# RGB_Bike_POV_v3.net
KiCad netlist of a schematic drawn in EAGLE
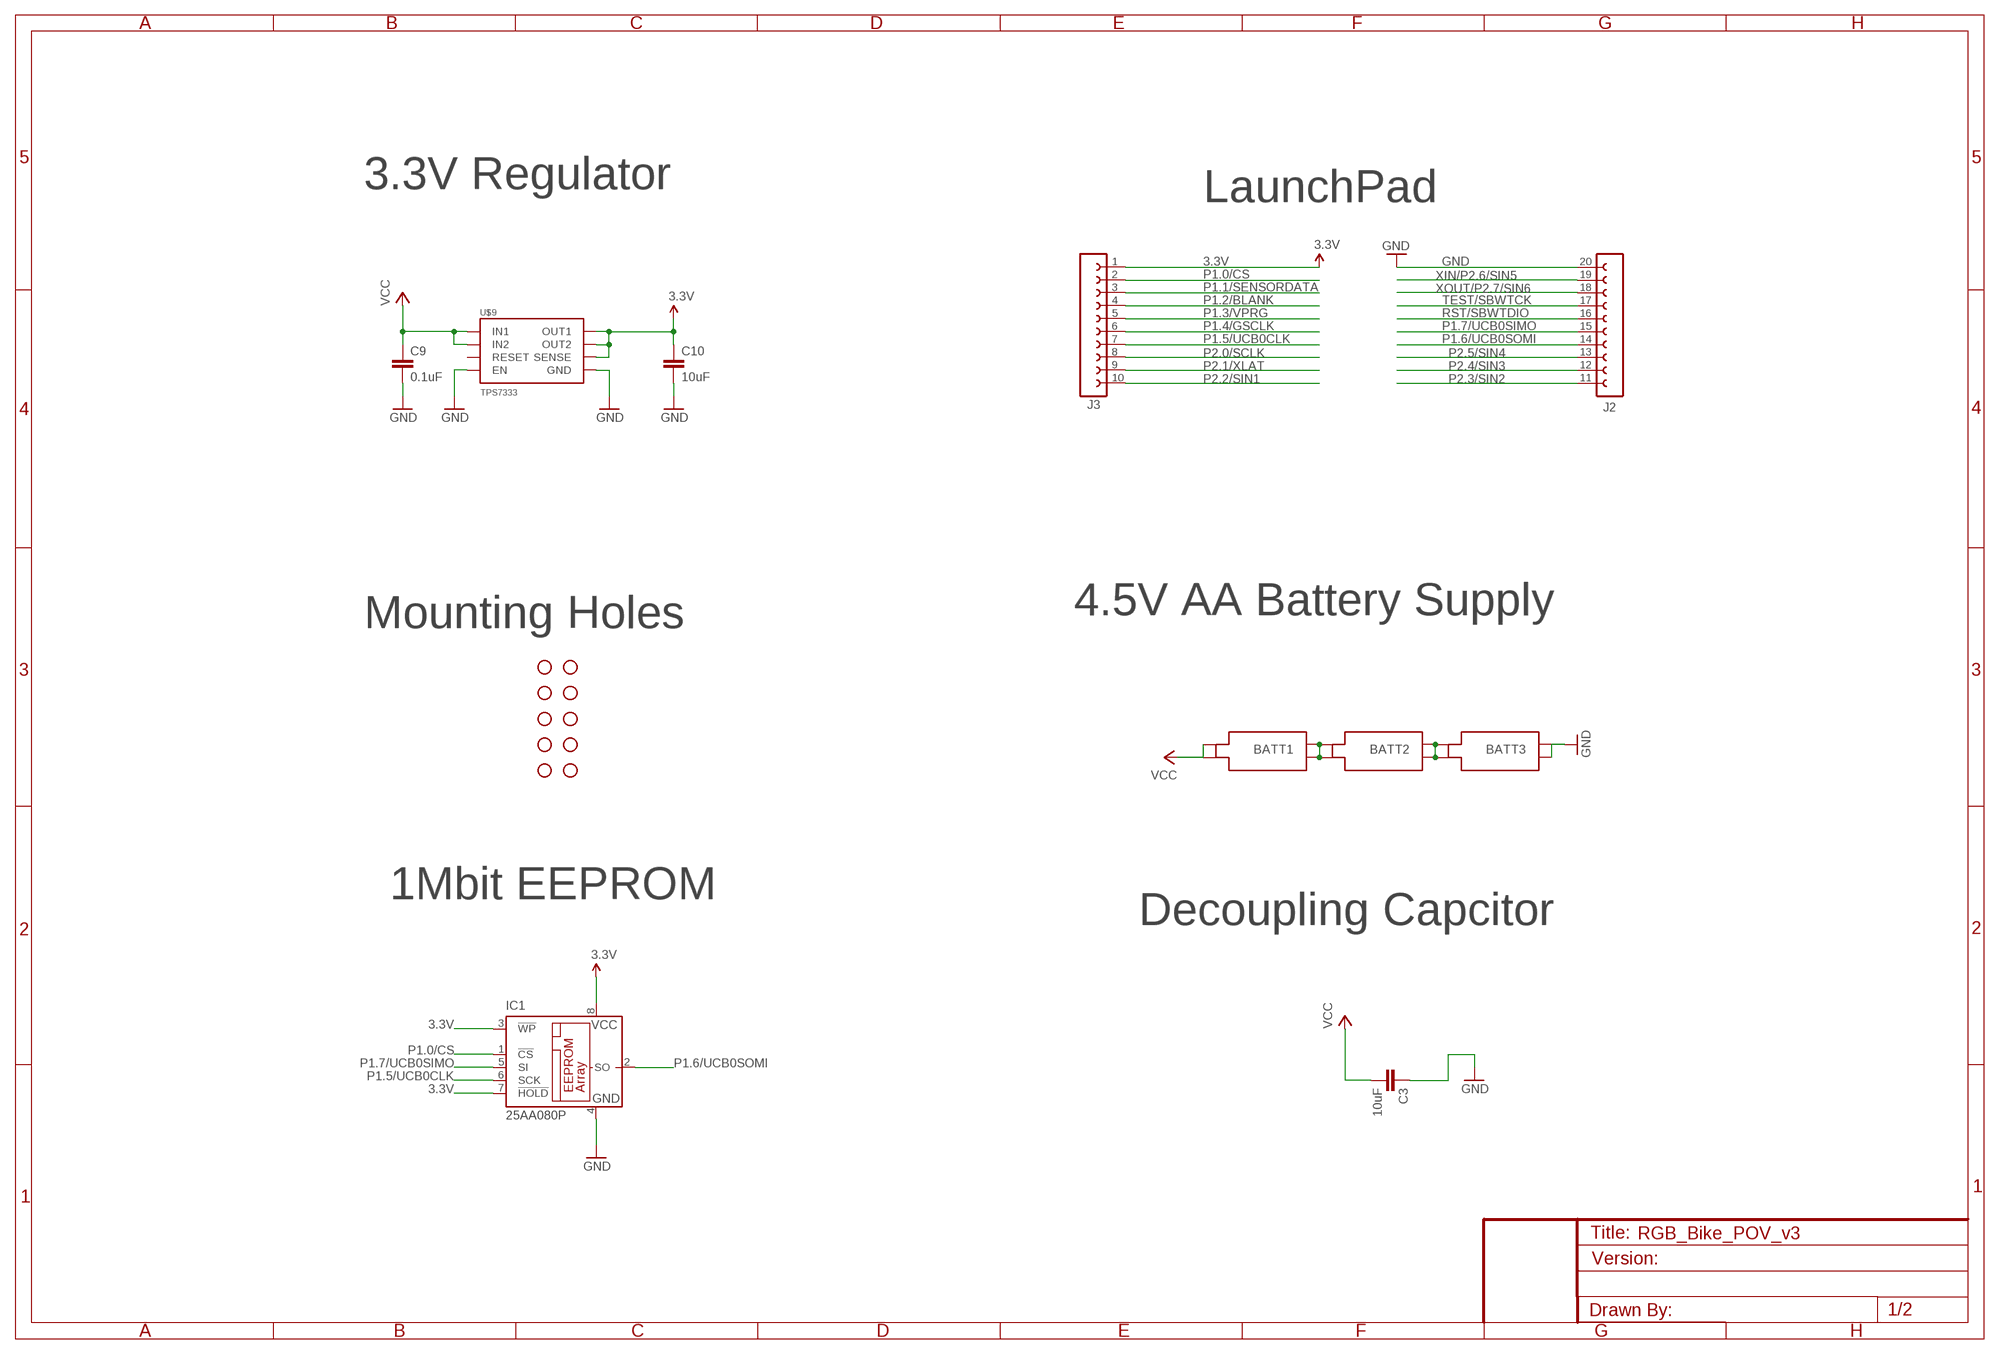
[diagram p0: schematic, sheet 1]
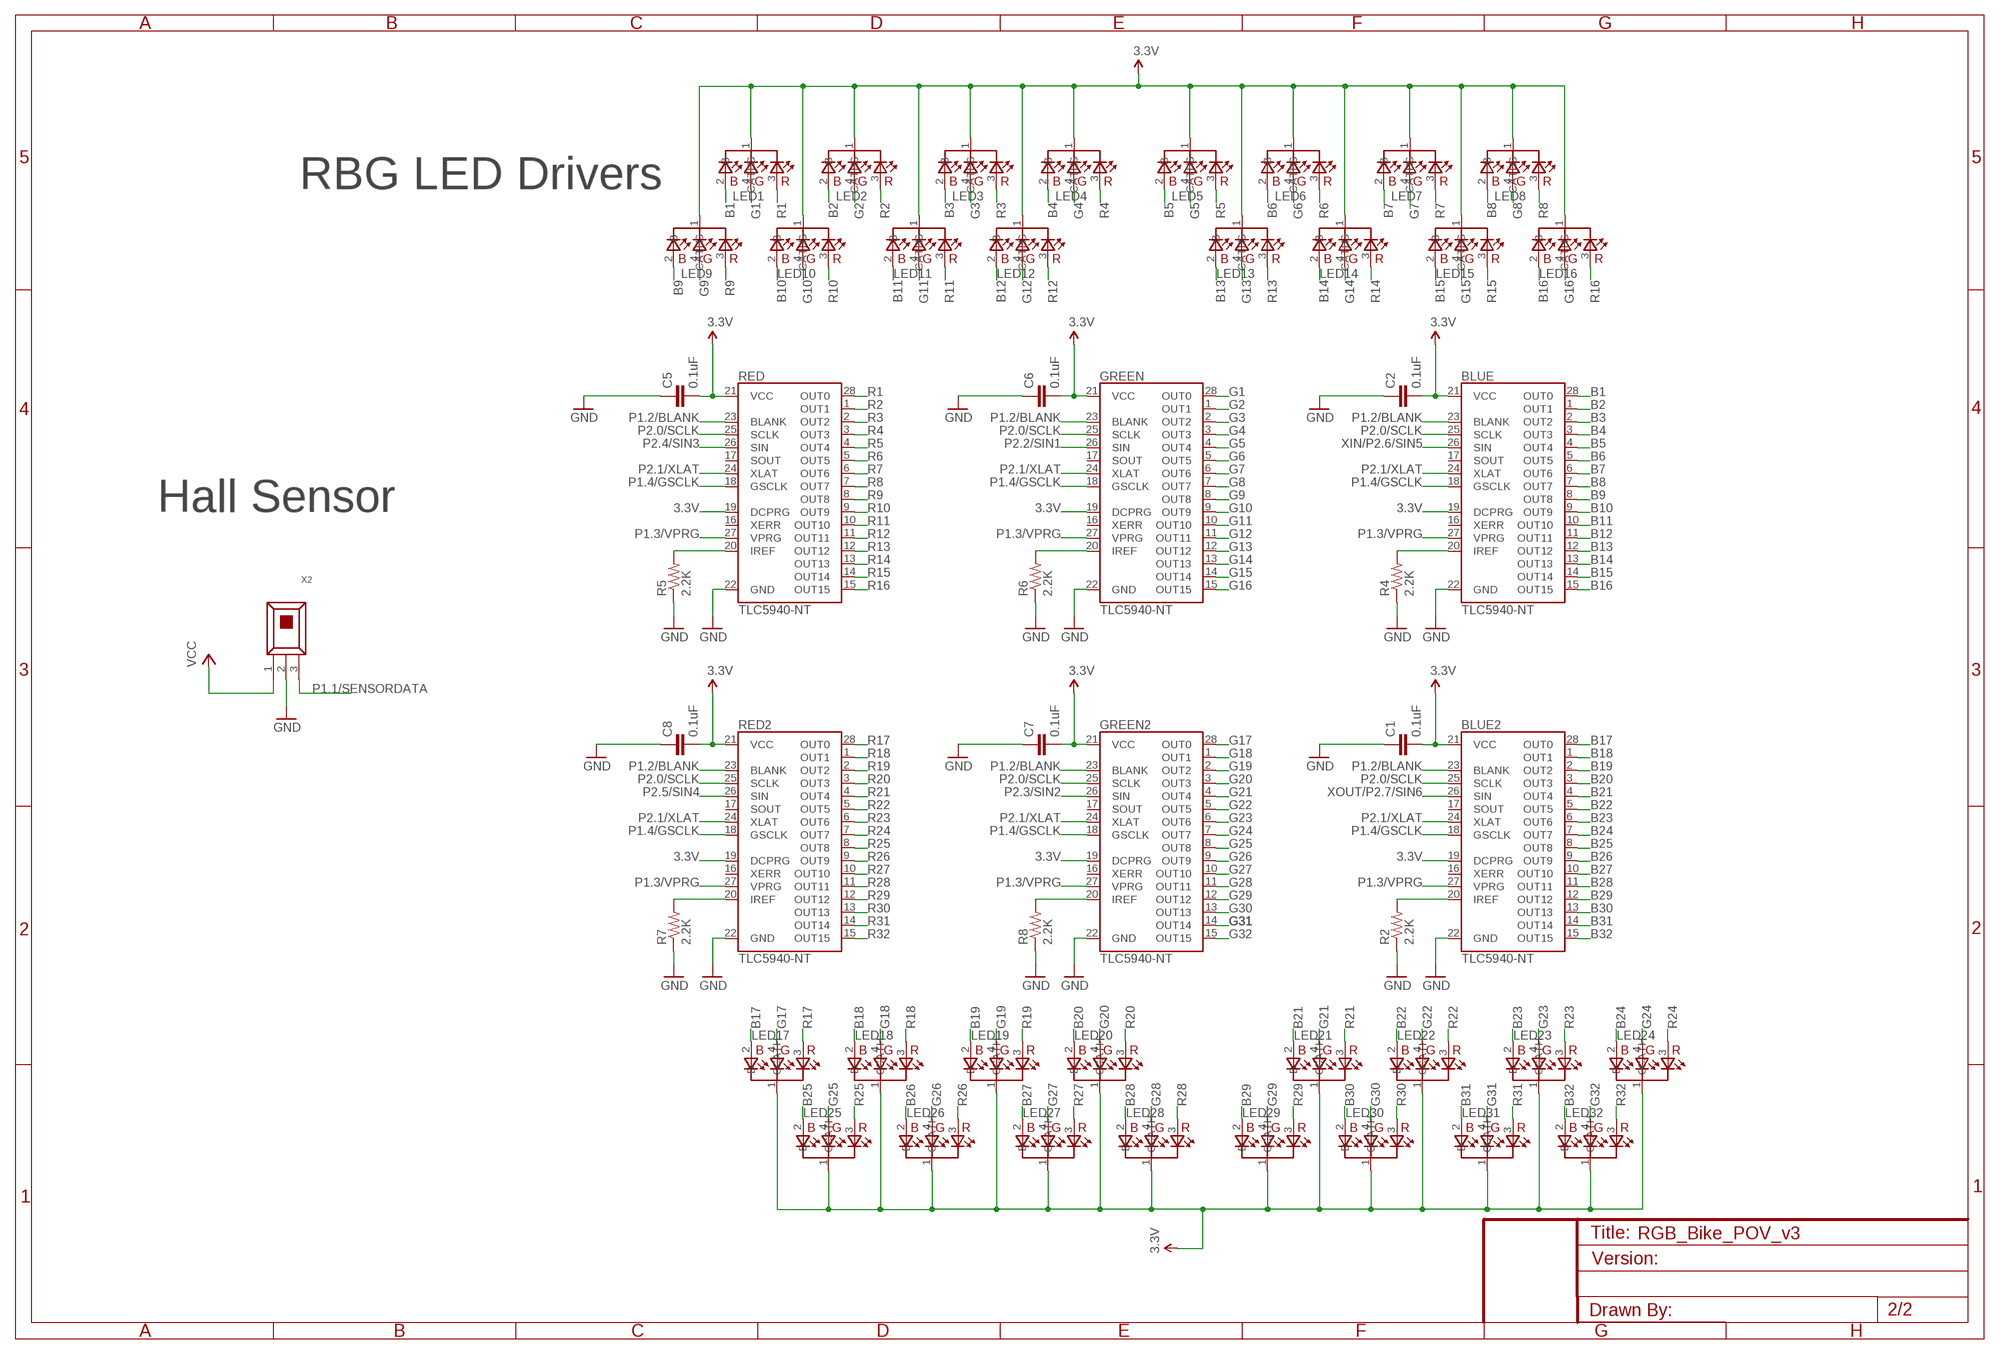
[diagram p1: schematic, sheet 2]

(export (version "E")
  (design (tool "Eeschema 10.0.6"))
  (components
    (comp (ref "BATT1")
      (value "1XAA")
      (footprint "eagle-import:1XAA")
      (libsource (lib "eagle-import") (part "1XAA"))
    )
    (comp (ref "BATT2")
      (value "1XAA")
      (footprint "eagle-import:1XAA")
      (libsource (lib "eagle-import") (part "1XAA"))
    )
    (comp (ref "BATT3")
      (value "1XAA")
      (footprint "eagle-import:1XAA")
      (libsource (lib "eagle-import") (part "1XAA"))
    )
    (comp (ref "C3")
      (value "10uF")
      (footprint "eagle-import:CAP-PTH-SMALL")
      (libsource (lib "eagle-import") (part "CAPPTH"))
    )
    (comp (ref "C9")
      (value "0.1uF")
      (footprint "eagle-import:CAP-PTH-SMALL")
      (libsource (lib "eagle-import") (part "CAPPTH"))
    )
    (comp (ref "C10")
      (value "10uF")
      (footprint "eagle-import:CAP-PTH-SMALL")
      (libsource (lib "eagle-import") (part "CAPPTH"))
    )
    (comp (ref "IC1")
      (value "25AA080P")
      (footprint "eagle-import:DIL8")
      (fields (field (name "MF") "MICROCHIP") (field (name "MPN") "25AA080/P"))
      (libsource (lib "eagle-import") (part "25PAA080"))
    )
    (comp (ref "J2")
      (value "FE10H")
      (footprint "eagle-import:FE10H")
      (libsource (lib "eagle-import") (part "FE10H"))
    )
    (comp (ref "J3")
      (value "FE10L")
      (footprint "eagle-import:FE10")
      (libsource (lib "eagle-import") (part "FE10L"))
    )
    (comp (ref "JP1")
      (value "STAND-OFF")
      (footprint "eagle-import:STAND-OFF")
      (libsource (lib "eagle-import") (part "STAND-OFF"))
    )
    (comp (ref "JP2")
      (value "STAND-OFF")
      (footprint "eagle-import:STAND-OFF")
      (libsource (lib "eagle-import") (part "STAND-OFF"))
    )
    (comp (ref "JP3")
      (value "STAND-OFF")
      (footprint "eagle-import:STAND-OFF")
      (libsource (lib "eagle-import") (part "STAND-OFF"))
    )
    (comp (ref "JP4")
      (value "STAND-OFF")
      (footprint "eagle-import:STAND-OFF")
      (libsource (lib "eagle-import") (part "STAND-OFF"))
    )
    (comp (ref "JP5")
      (value "STAND-OFF")
      (footprint "eagle-import:STAND-OFF")
      (libsource (lib "eagle-import") (part "STAND-OFF"))
    )
    (comp (ref "JP7")
      (value "STAND-OFF")
      (footprint "eagle-import:STAND-OFF")
      (libsource (lib "eagle-import") (part "STAND-OFF"))
    )
    (comp (ref "JP25")
      (value "STAND-OFF")
      (footprint "eagle-import:STAND-OFF")
      (libsource (lib "eagle-import") (part "STAND-OFF"))
    )
    (comp (ref "JP26")
      (value "STAND-OFF")
      (footprint "eagle-import:STAND-OFF")
      (libsource (lib "eagle-import") (part "STAND-OFF"))
    )
    (comp (ref "JP27")
      (value "STAND-OFF")
      (footprint "eagle-import:STAND-OFF")
      (libsource (lib "eagle-import") (part "STAND-OFF"))
    )
    (comp (ref "JP28")
      (value "STAND-OFF")
      (footprint "eagle-import:STAND-OFF")
      (libsource (lib "eagle-import") (part "STAND-OFF"))
    )
    (comp (ref "U$9")
      (value "TPS7333")
      (footprint "eagle-import:TPS7333")
      (libsource (lib "eagle-import") (part "TPS7333"))
    )
    (comp (ref "BLUE")
      (value "TLC5940-NT")
      (footprint "eagle-import:DIL28-3")
      (libsource (lib "eagle-import") (part "TLC5940-NT"))
    )
    (comp (ref "BLUE2")
      (value "TLC5940-NT")
      (footprint "eagle-import:DIL28-3")
      (libsource (lib "eagle-import") (part "TLC5940-NT"))
    )
    (comp (ref "C1")
      (value "0.1uF")
      (footprint "eagle-import:CAP-PTH-SMALL")
      (libsource (lib "eagle-import") (part "CAPPTH"))
    )
    (comp (ref "C2")
      (value "0.1uF")
      (footprint "eagle-import:CAP-PTH-SMALL")
      (libsource (lib "eagle-import") (part "CAPPTH"))
    )
    (comp (ref "C5")
      (value "0.1uF")
      (footprint "eagle-import:CAP-PTH-SMALL")
      (libsource (lib "eagle-import") (part "CAPPTH"))
    )
    (comp (ref "C6")
      (value "0.1uF")
      (footprint "eagle-import:CAP-PTH-SMALL")
      (libsource (lib "eagle-import") (part "CAPPTH"))
    )
    (comp (ref "C7")
      (value "0.1uF")
      (footprint "eagle-import:CAP-PTH-SMALL")
      (libsource (lib "eagle-import") (part "CAPPTH"))
    )
    (comp (ref "C8")
      (value "0.1uF")
      (footprint "eagle-import:CAP-PTH-SMALL")
      (libsource (lib "eagle-import") (part "CAPPTH"))
    )
    (comp (ref "GREEN")
      (value "TLC5940-NT")
      (footprint "eagle-import:DIL28-3")
      (libsource (lib "eagle-import") (part "TLC5940-NT"))
    )
    (comp (ref "GREEN2")
      (value "TLC5940-NT")
      (footprint "eagle-import:DIL28-3")
      (libsource (lib "eagle-import") (part "TLC5940-NT"))
    )
    (comp (ref "LED1")
      (value "LED_SUPERFLUX_RGB_CATH")
      (footprint "eagle-import:LED_SUPERFLUX")
      (libsource (lib "eagle-import") (part "LED_SUPERFLUX_RGB_CATH"))
    )
    (comp (ref "LED2")
      (value "LED_SUPERFLUX_RGB_CATH")
      (footprint "eagle-import:LED_SUPERFLUX")
      (libsource (lib "eagle-import") (part "LED_SUPERFLUX_RGB_CATH"))
    )
    (comp (ref "LED3")
      (value "LED_SUPERFLUX_RGB_CATH")
      (footprint "eagle-import:LED_SUPERFLUX")
      (libsource (lib "eagle-import") (part "LED_SUPERFLUX_RGB_CATH"))
    )
    (comp (ref "LED4")
      (value "LED_SUPERFLUX_RGB_CATH")
      (footprint "eagle-import:LED_SUPERFLUX")
      (libsource (lib "eagle-import") (part "LED_SUPERFLUX_RGB_CATH"))
    )
    (comp (ref "LED5")
      (value "LED_SUPERFLUX_RGB_CATH")
      (footprint "eagle-import:LED_SUPERFLUX")
      (libsource (lib "eagle-import") (part "LED_SUPERFLUX_RGB_CATH"))
    )
    (comp (ref "LED6")
      (value "LED_SUPERFLUX_RGB_CATH")
      (footprint "eagle-import:LED_SUPERFLUX")
      (libsource (lib "eagle-import") (part "LED_SUPERFLUX_RGB_CATH"))
    )
    (comp (ref "LED7")
      (value "LED_SUPERFLUX_RGB_CATH")
      (footprint "eagle-import:LED_SUPERFLUX")
      (libsource (lib "eagle-import") (part "LED_SUPERFLUX_RGB_CATH"))
    )
    (comp (ref "LED8")
      (value "LED_SUPERFLUX_RGB_CATH")
      (footprint "eagle-import:LED_SUPERFLUX")
      (libsource (lib "eagle-import") (part "LED_SUPERFLUX_RGB_CATH"))
    )
    (comp (ref "LED9")
      (value "LED_SUPERFLUX_RGB_CATH")
      (footprint "eagle-import:LED_SUPERFLUX")
      (libsource (lib "eagle-import") (part "LED_SUPERFLUX_RGB_CATH"))
    )
    (comp (ref "LED10")
      (value "LED_SUPERFLUX_RGB_CATH")
      (footprint "eagle-import:LED_SUPERFLUX")
      (libsource (lib "eagle-import") (part "LED_SUPERFLUX_RGB_CATH"))
    )
    (comp (ref "LED11")
      (value "LED_SUPERFLUX_RGB_CATH")
      (footprint "eagle-import:LED_SUPERFLUX")
      (libsource (lib "eagle-import") (part "LED_SUPERFLUX_RGB_CATH"))
    )
    (comp (ref "LED12")
      (value "LED_SUPERFLUX_RGB_CATH")
      (footprint "eagle-import:LED_SUPERFLUX")
      (libsource (lib "eagle-import") (part "LED_SUPERFLUX_RGB_CATH"))
    )
    (comp (ref "LED13")
      (value "LED_SUPERFLUX_RGB_CATH")
      (footprint "eagle-import:LED_SUPERFLUX")
      (libsource (lib "eagle-import") (part "LED_SUPERFLUX_RGB_CATH"))
    )
    (comp (ref "LED14")
      (value "LED_SUPERFLUX_RGB_CATH")
      (footprint "eagle-import:LED_SUPERFLUX")
      (libsource (lib "eagle-import") (part "LED_SUPERFLUX_RGB_CATH"))
    )
    (comp (ref "LED15")
      (value "LED_SUPERFLUX_RGB_CATH")
      (footprint "eagle-import:LED_SUPERFLUX")
      (libsource (lib "eagle-import") (part "LED_SUPERFLUX_RGB_CATH"))
    )
    (comp (ref "LED16")
      (value "LED_SUPERFLUX_RGB_CATH")
      (footprint "eagle-import:LED_SUPERFLUX")
      (libsource (lib "eagle-import") (part "LED_SUPERFLUX_RGB_CATH"))
    )
    (comp (ref "LED17")
      (value "LED_SUPERFLUX_RGB_CATH")
      (footprint "eagle-import:LED_SUPERFLUX")
      (libsource (lib "eagle-import") (part "LED_SUPERFLUX_RGB_CATH"))
    )
    (comp (ref "LED18")
      (value "LED_SUPERFLUX_RGB_CATH")
      (footprint "eagle-import:LED_SUPERFLUX")
      (libsource (lib "eagle-import") (part "LED_SUPERFLUX_RGB_CATH"))
    )
    (comp (ref "LED19")
      (value "LED_SUPERFLUX_RGB_CATH")
      (footprint "eagle-import:LED_SUPERFLUX")
      (libsource (lib "eagle-import") (part "LED_SUPERFLUX_RGB_CATH"))
    )
    (comp (ref "LED20")
      (value "LED_SUPERFLUX_RGB_CATH")
      (footprint "eagle-import:LED_SUPERFLUX")
      (libsource (lib "eagle-import") (part "LED_SUPERFLUX_RGB_CATH"))
    )
    (comp (ref "LED21")
      (value "LED_SUPERFLUX_RGB_CATH")
      (footprint "eagle-import:LED_SUPERFLUX")
      (libsource (lib "eagle-import") (part "LED_SUPERFLUX_RGB_CATH"))
    )
    (comp (ref "LED22")
      (value "LED_SUPERFLUX_RGB_CATH")
      (footprint "eagle-import:LED_SUPERFLUX")
      (libsource (lib "eagle-import") (part "LED_SUPERFLUX_RGB_CATH"))
    )
    (comp (ref "LED23")
      (value "LED_SUPERFLUX_RGB_CATH")
      (footprint "eagle-import:LED_SUPERFLUX")
      (libsource (lib "eagle-import") (part "LED_SUPERFLUX_RGB_CATH"))
    )
    (comp (ref "LED24")
      (value "LED_SUPERFLUX_RGB_CATH")
      (footprint "eagle-import:LED_SUPERFLUX")
      (libsource (lib "eagle-import") (part "LED_SUPERFLUX_RGB_CATH"))
    )
    (comp (ref "LED25")
      (value "LED_SUPERFLUX_RGB_CATH")
      (footprint "eagle-import:LED_SUPERFLUX")
      (libsource (lib "eagle-import") (part "LED_SUPERFLUX_RGB_CATH"))
    )
    (comp (ref "LED26")
      (value "LED_SUPERFLUX_RGB_CATH")
      (footprint "eagle-import:LED_SUPERFLUX")
      (libsource (lib "eagle-import") (part "LED_SUPERFLUX_RGB_CATH"))
    )
    (comp (ref "LED27")
      (value "LED_SUPERFLUX_RGB_CATH")
      (footprint "eagle-import:LED_SUPERFLUX")
      (libsource (lib "eagle-import") (part "LED_SUPERFLUX_RGB_CATH"))
    )
    (comp (ref "LED28")
      (value "LED_SUPERFLUX_RGB_CATH")
      (footprint "eagle-import:LED_SUPERFLUX")
      (libsource (lib "eagle-import") (part "LED_SUPERFLUX_RGB_CATH"))
    )
    (comp (ref "LED29")
      (value "LED_SUPERFLUX_RGB_CATH")
      (footprint "eagle-import:LED_SUPERFLUX")
      (libsource (lib "eagle-import") (part "LED_SUPERFLUX_RGB_CATH"))
    )
    (comp (ref "LED30")
      (value "LED_SUPERFLUX_RGB_CATH")
      (footprint "eagle-import:LED_SUPERFLUX")
      (libsource (lib "eagle-import") (part "LED_SUPERFLUX_RGB_CATH"))
    )
    (comp (ref "LED31")
      (value "LED_SUPERFLUX_RGB_CATH")
      (footprint "eagle-import:LED_SUPERFLUX")
      (libsource (lib "eagle-import") (part "LED_SUPERFLUX_RGB_CATH"))
    )
    (comp (ref "LED32")
      (value "LED_SUPERFLUX_RGB_CATH")
      (footprint "eagle-import:LED_SUPERFLUX")
      (libsource (lib "eagle-import") (part "LED_SUPERFLUX_RGB_CATH"))
    )
    (comp (ref "R2")
      (value "2.2K")
      (footprint "eagle-import:1_6W-RES")
      (libsource (lib "eagle-import") (part "RESISTORPTH-1/6W"))
    )
    (comp (ref "R4")
      (value "2.2K")
      (footprint "eagle-import:1_6W-RES")
      (libsource (lib "eagle-import") (part "RESISTORPTH-1/6W"))
    )
    (comp (ref "R5")
      (value "2.2K")
      (footprint "eagle-import:1_6W-RES")
      (libsource (lib "eagle-import") (part "RESISTORPTH-1/6W"))
    )
    (comp (ref "R6")
      (value "2.2K")
      (footprint "eagle-import:1_6W-RES")
      (libsource (lib "eagle-import") (part "RESISTORPTH-1/6W"))
    )
    (comp (ref "R7")
      (value "2.2K")
      (footprint "eagle-import:1_6W-RES")
      (libsource (lib "eagle-import") (part "RESISTORPTH-1/6W"))
    )
    (comp (ref "R8")
      (value "2.2K")
      (footprint "eagle-import:1_6W-RES")
      (libsource (lib "eagle-import") (part "RESISTORPTH-1/6W"))
    )
    (comp (ref "RED")
      (value "TLC5940-NT")
      (footprint "eagle-import:DIL28-3")
      (libsource (lib "eagle-import") (part "TLC5940-NT"))
    )
    (comp (ref "RED2")
      (value "TLC5940-NT")
      (footprint "eagle-import:DIL28-3")
      (libsource (lib "eagle-import") (part "TLC5940-NT"))
    )
    (comp (ref "X2")
      (value "HALLEFFECT")
      (footprint "eagle-import:3SIP")
      (libsource (lib "eagle-import") (part "HALLEFFECT"))
    )
  )
  (nets
    (net (code "1") (name "3.3V") (class "Default")
      (node (ref "BLUE") (pin "19") (pinfunction "DCPRG_19") (pintype "bidirectional"))
      (node (ref "BLUE") (pin "21") (pinfunction "VCC_21") (pintype "bidirectional"))
      (node (ref "BLUE2") (pin "19") (pinfunction "DCPRG_19") (pintype "bidirectional"))
      (node (ref "BLUE2") (pin "21") (pinfunction "VCC_21") (pintype "bidirectional"))
      (node (ref "C1") (pin "2") (pinfunction "2_2") (pintype "passive"))
      (node (ref "C10") (pin "1") (pinfunction "1_1") (pintype "passive"))
      (node (ref "C2") (pin "2") (pinfunction "2_2") (pintype "passive"))
      (node (ref "C5") (pin "2") (pinfunction "2_2") (pintype "passive"))
      (node (ref "C6") (pin "2") (pinfunction "2_2") (pintype "passive"))
      (node (ref "C7") (pin "2") (pinfunction "2_2") (pintype "passive"))
      (node (ref "C8") (pin "2") (pinfunction "2_2") (pintype "passive"))
      (node (ref "GREEN") (pin "19") (pinfunction "DCPRG_19") (pintype "bidirectional"))
      (node (ref "GREEN") (pin "21") (pinfunction "VCC_21") (pintype "bidirectional"))
      (node (ref "GREEN2") (pin "19") (pinfunction "DCPRG_19") (pintype "bidirectional"))
      (node (ref "GREEN2") (pin "21") (pinfunction "VCC_21") (pintype "bidirectional"))
      (node (ref "IC1") (pin "3") (pinfunction "~{WP}_3") (pintype "input"))
      (node (ref "IC1") (pin "7") (pinfunction "~{HOLD}_7") (pintype "input"))
      (node (ref "IC1") (pin "8") (pinfunction "VCC_8") (pintype "power_in"))
      (node (ref "J3") (pin "1") (pinfunction "1_1") (pintype "passive"))
      (node (ref "LED1") (pin "1") (pinfunction "CATH_1") (pintype "bidirectional"))
      (node (ref "LED10") (pin "1") (pinfunction "CATH_1") (pintype "bidirectional"))
      (node (ref "LED11") (pin "1") (pinfunction "CATH_1") (pintype "bidirectional"))
      (node (ref "LED12") (pin "1") (pinfunction "CATH_1") (pintype "bidirectional"))
      (node (ref "LED13") (pin "1") (pinfunction "CATH_1") (pintype "bidirectional"))
      (node (ref "LED14") (pin "1") (pinfunction "CATH_1") (pintype "bidirectional"))
      (node (ref "LED15") (pin "1") (pinfunction "CATH_1") (pintype "bidirectional"))
      (node (ref "LED16") (pin "1") (pinfunction "CATH_1") (pintype "bidirectional"))
      (node (ref "LED17") (pin "1") (pinfunction "CATH_1") (pintype "bidirectional"))
      (node (ref "LED18") (pin "1") (pinfunction "CATH_1") (pintype "bidirectional"))
      (node (ref "LED19") (pin "1") (pinfunction "CATH_1") (pintype "bidirectional"))
      (node (ref "LED2") (pin "1") (pinfunction "CATH_1") (pintype "bidirectional"))
      (node (ref "LED20") (pin "1") (pinfunction "CATH_1") (pintype "bidirectional"))
      (node (ref "LED21") (pin "1") (pinfunction "CATH_1") (pintype "bidirectional"))
      (node (ref "LED22") (pin "1") (pinfunction "CATH_1") (pintype "bidirectional"))
      (node (ref "LED23") (pin "1") (pinfunction "CATH_1") (pintype "bidirectional"))
      (node (ref "LED24") (pin "1") (pinfunction "CATH_1") (pintype "bidirectional"))
      (node (ref "LED25") (pin "1") (pinfunction "CATH_1") (pintype "bidirectional"))
      (node (ref "LED26") (pin "1") (pinfunction "CATH_1") (pintype "bidirectional"))
      (node (ref "LED27") (pin "1") (pinfunction "CATH_1") (pintype "bidirectional"))
      (node (ref "LED28") (pin "1") (pinfunction "CATH_1") (pintype "bidirectional"))
      (node (ref "LED29") (pin "1") (pinfunction "CATH_1") (pintype "bidirectional"))
      (node (ref "LED3") (pin "1") (pinfunction "CATH_1") (pintype "bidirectional"))
      (node (ref "LED30") (pin "1") (pinfunction "CATH_1") (pintype "bidirectional"))
      (node (ref "LED31") (pin "1") (pinfunction "CATH_1") (pintype "bidirectional"))
      (node (ref "LED32") (pin "1") (pinfunction "CATH_1") (pintype "bidirectional"))
      (node (ref "LED4") (pin "1") (pinfunction "CATH_1") (pintype "bidirectional"))
      (node (ref "LED5") (pin "1") (pinfunction "CATH_1") (pintype "bidirectional"))
      (node (ref "LED6") (pin "1") (pinfunction "CATH_1") (pintype "bidirectional"))
      (node (ref "LED7") (pin "1") (pinfunction "CATH_1") (pintype "bidirectional"))
      (node (ref "LED8") (pin "1") (pinfunction "CATH_1") (pintype "bidirectional"))
      (node (ref "LED9") (pin "1") (pinfunction "CATH_1") (pintype "bidirectional"))
      (node (ref "RED") (pin "19") (pinfunction "DCPRG_19") (pintype "bidirectional"))
      (node (ref "RED") (pin "21") (pinfunction "VCC_21") (pintype "bidirectional"))
      (node (ref "RED2") (pin "19") (pinfunction "DCPRG_19") (pintype "bidirectional"))
      (node (ref "RED2") (pin "21") (pinfunction "VCC_21") (pintype "bidirectional"))
      (node (ref "U$9") (pin "5") (pinfunction "OUT1_5") (pintype "bidirectional"))
      (node (ref "U$9") (pin "6") (pinfunction "OUT2_6") (pintype "bidirectional"))
      (node (ref "U$9") (pin "7") (pinfunction "SENSE_7") (pintype "bidirectional"))
    )
    (net (code "2") (name "B1") (class "Default")
      (node (ref "BLUE") (pin "28") (pinfunction "OUT0_28") (pintype "bidirectional"))
      (node (ref "LED1") (pin "2") (pinfunction "B_2") (pintype "bidirectional"))
    )
    (net (code "3") (name "B2") (class "Default")
      (node (ref "BLUE") (pin "1") (pinfunction "OUT1_1") (pintype "bidirectional"))
      (node (ref "LED2") (pin "2") (pinfunction "B_2") (pintype "bidirectional"))
    )
    (net (code "4") (name "B3") (class "Default")
      (node (ref "BLUE") (pin "2") (pinfunction "OUT2_2") (pintype "bidirectional"))
      (node (ref "LED3") (pin "2") (pinfunction "B_2") (pintype "bidirectional"))
    )
    (net (code "5") (name "B4") (class "Default")
      (node (ref "BLUE") (pin "3") (pinfunction "OUT3_3") (pintype "bidirectional"))
      (node (ref "LED4") (pin "2") (pinfunction "B_2") (pintype "bidirectional"))
    )
    (net (code "6") (name "B5") (class "Default")
      (node (ref "BLUE") (pin "4") (pinfunction "OUT4_4") (pintype "bidirectional"))
      (node (ref "LED5") (pin "2") (pinfunction "B_2") (pintype "bidirectional"))
    )
    (net (code "7") (name "B6") (class "Default")
      (node (ref "BLUE") (pin "5") (pinfunction "OUT5_5") (pintype "bidirectional"))
      (node (ref "LED6") (pin "2") (pinfunction "B_2") (pintype "bidirectional"))
    )
    (net (code "8") (name "B7") (class "Default")
      (node (ref "BLUE") (pin "6") (pinfunction "OUT6_6") (pintype "bidirectional"))
      (node (ref "LED7") (pin "2") (pinfunction "B_2") (pintype "bidirectional"))
    )
    (net (code "9") (name "B8") (class "Default")
      (node (ref "BLUE") (pin "7") (pinfunction "OUT7_7") (pintype "bidirectional"))
      (node (ref "LED8") (pin "2") (pinfunction "B_2") (pintype "bidirectional"))
    )
    (net (code "10") (name "B9") (class "Default")
      (node (ref "BLUE") (pin "8") (pinfunction "OUT8_8") (pintype "bidirectional"))
      (node (ref "LED9") (pin "2") (pinfunction "B_2") (pintype "bidirectional"))
    )
    (net (code "11") (name "B10") (class "Default")
      (node (ref "BLUE") (pin "9") (pinfunction "OUT9_9") (pintype "bidirectional"))
      (node (ref "LED10") (pin "2") (pinfunction "B_2") (pintype "bidirectional"))
    )
    (net (code "12") (name "B11") (class "Default")
      (node (ref "BLUE") (pin "10") (pinfunction "OUT10_10") (pintype "bidirectional"))
      (node (ref "LED11") (pin "2") (pinfunction "B_2") (pintype "bidirectional"))
    )
    (net (code "13") (name "B12") (class "Default")
      (node (ref "BLUE") (pin "11") (pinfunction "OUT11_11") (pintype "bidirectional"))
      (node (ref "LED12") (pin "2") (pinfunction "B_2") (pintype "bidirectional"))
    )
    (net (code "14") (name "B13") (class "Default")
      (node (ref "BLUE") (pin "12") (pinfunction "OUT12_12") (pintype "bidirectional"))
      (node (ref "LED13") (pin "2") (pinfunction "B_2") (pintype "bidirectional"))
    )
    (net (code "15") (name "B14") (class "Default")
      (node (ref "BLUE") (pin "13") (pinfunction "OUT13_13") (pintype "bidirectional"))
      (node (ref "LED14") (pin "2") (pinfunction "B_2") (pintype "bidirectional"))
    )
    (net (code "16") (name "B15") (class "Default")
      (node (ref "BLUE") (pin "14") (pinfunction "OUT14_14") (pintype "bidirectional"))
      (node (ref "LED15") (pin "2") (pinfunction "B_2") (pintype "bidirectional"))
    )
    (net (code "17") (name "B16") (class "Default")
      (node (ref "BLUE") (pin "15") (pinfunction "OUT15_15") (pintype "bidirectional"))
      (node (ref "LED16") (pin "2") (pinfunction "B_2") (pintype "bidirectional"))
    )
    (net (code "18") (name "B17") (class "Default")
      (node (ref "BLUE2") (pin "28") (pinfunction "OUT0_28") (pintype "bidirectional"))
      (node (ref "LED17") (pin "2") (pinfunction "B_2") (pintype "bidirectional"))
    )
    (net (code "19") (name "B18") (class "Default")
      (node (ref "BLUE2") (pin "1") (pinfunction "OUT1_1") (pintype "bidirectional"))
      (node (ref "LED18") (pin "2") (pinfunction "B_2") (pintype "bidirectional"))
    )
    (net (code "20") (name "B19") (class "Default")
      (node (ref "BLUE2") (pin "2") (pinfunction "OUT2_2") (pintype "bidirectional"))
      (node (ref "LED19") (pin "2") (pinfunction "B_2") (pintype "bidirectional"))
    )
    (net (code "21") (name "B20") (class "Default")
      (node (ref "BLUE2") (pin "3") (pinfunction "OUT3_3") (pintype "bidirectional"))
      (node (ref "LED20") (pin "2") (pinfunction "B_2") (pintype "bidirectional"))
    )
    (net (code "22") (name "B21") (class "Default")
      (node (ref "BLUE2") (pin "4") (pinfunction "OUT4_4") (pintype "bidirectional"))
      (node (ref "LED21") (pin "2") (pinfunction "B_2") (pintype "bidirectional"))
    )
    (net (code "23") (name "B22") (class "Default")
      (node (ref "BLUE2") (pin "5") (pinfunction "OUT5_5") (pintype "bidirectional"))
      (node (ref "LED22") (pin "2") (pinfunction "B_2") (pintype "bidirectional"))
    )
    (net (code "24") (name "B23") (class "Default")
      (node (ref "BLUE2") (pin "6") (pinfunction "OUT6_6") (pintype "bidirectional"))
      (node (ref "LED23") (pin "2") (pinfunction "B_2") (pintype "bidirectional"))
    )
    (net (code "25") (name "B24") (class "Default")
      (node (ref "BLUE2") (pin "7") (pinfunction "OUT7_7") (pintype "bidirectional"))
      (node (ref "LED24") (pin "2") (pinfunction "B_2") (pintype "bidirectional"))
    )
    (net (code "26") (name "B25") (class "Default")
      (node (ref "BLUE2") (pin "8") (pinfunction "OUT8_8") (pintype "bidirectional"))
      (node (ref "LED25") (pin "2") (pinfunction "B_2") (pintype "bidirectional"))
    )
    (net (code "27") (name "B26") (class "Default")
      (node (ref "BLUE2") (pin "9") (pinfunction "OUT9_9") (pintype "bidirectional"))
      (node (ref "LED26") (pin "2") (pinfunction "B_2") (pintype "bidirectional"))
    )
    (net (code "28") (name "B27") (class "Default")
      (node (ref "BLUE2") (pin "10") (pinfunction "OUT10_10") (pintype "bidirectional"))
      (node (ref "LED27") (pin "2") (pinfunction "B_2") (pintype "bidirectional"))
    )
    (net (code "29") (name "B28") (class "Default")
      (node (ref "BLUE2") (pin "11") (pinfunction "OUT11_11") (pintype "bidirectional"))
      (node (ref "LED28") (pin "2") (pinfunction "B_2") (pintype "bidirectional"))
    )
    (net (code "30") (name "B29") (class "Default")
      (node (ref "BLUE2") (pin "12") (pinfunction "OUT12_12") (pintype "bidirectional"))
      (node (ref "LED29") (pin "2") (pinfunction "B_2") (pintype "bidirectional"))
    )
    (net (code "31") (name "B30") (class "Default")
      (node (ref "BLUE2") (pin "13") (pinfunction "OUT13_13") (pintype "bidirectional"))
      (node (ref "LED30") (pin "2") (pinfunction "B_2") (pintype "bidirectional"))
    )
    (net (code "32") (name "B31") (class "Default")
      (node (ref "BLUE2") (pin "14") (pinfunction "OUT14_14") (pintype "bidirectional"))
      (node (ref "LED31") (pin "2") (pinfunction "B_2") (pintype "bidirectional"))
    )
    (net (code "33") (name "B32") (class "Default")
      (node (ref "BLUE2") (pin "15") (pinfunction "OUT15_15") (pintype "bidirectional"))
      (node (ref "LED32") (pin "2") (pinfunction "B_2") (pintype "bidirectional"))
    )
    (net (code "34") (name "G1") (class "Default")
      (node (ref "GREEN") (pin "28") (pinfunction "OUT0_28") (pintype "bidirectional"))
      (node (ref "LED1") (pin "4") (pinfunction "G_4") (pintype "bidirectional"))
    )
    (net (code "35") (name "G2") (class "Default")
      (node (ref "GREEN") (pin "1") (pinfunction "OUT1_1") (pintype "bidirectional"))
      (node (ref "LED2") (pin "4") (pinfunction "G_4") (pintype "bidirectional"))
    )
    (net (code "36") (name "G3") (class "Default")
      (node (ref "GREEN") (pin "2") (pinfunction "OUT2_2") (pintype "bidirectional"))
      (node (ref "LED3") (pin "4") (pinfunction "G_4") (pintype "bidirectional"))
    )
    (net (code "37") (name "G4") (class "Default")
      (node (ref "GREEN") (pin "3") (pinfunction "OUT3_3") (pintype "bidirectional"))
      (node (ref "LED4") (pin "4") (pinfunction "G_4") (pintype "bidirectional"))
    )
    (net (code "38") (name "G5") (class "Default")
      (node (ref "GREEN") (pin "4") (pinfunction "OUT4_4") (pintype "bidirectional"))
      (node (ref "LED5") (pin "4") (pinfunction "G_4") (pintype "bidirectional"))
    )
    (net (code "39") (name "G6") (class "Default")
      (node (ref "GREEN") (pin "5") (pinfunction "OUT5_5") (pintype "bidirectional"))
      (node (ref "LED6") (pin "4") (pinfunction "G_4") (pintype "bidirectional"))
    )
    (net (code "40") (name "G7") (class "Default")
      (node (ref "GREEN") (pin "6") (pinfunction "OUT6_6") (pintype "bidirectional"))
      (node (ref "LED7") (pin "4") (pinfunction "G_4") (pintype "bidirectional"))
    )
    (net (code "41") (name "G8") (class "Default")
      (node (ref "GREEN") (pin "7") (pinfunction "OUT7_7") (pintype "bidirectional"))
      (node (ref "LED8") (pin "4") (pinfunction "G_4") (pintype "bidirectional"))
    )
    (net (code "42") (name "G9") (class "Default")
      (node (ref "GREEN") (pin "8") (pinfunction "OUT8_8") (pintype "bidirectional"))
      (node (ref "LED9") (pin "4") (pinfunction "G_4") (pintype "bidirectional"))
    )
    (net (code "43") (name "G10") (class "Default")
      (node (ref "GREEN") (pin "9") (pinfunction "OUT9_9") (pintype "bidirectional"))
      (node (ref "LED10") (pin "4") (pinfunction "G_4") (pintype "bidirectional"))
    )
    (net (code "44") (name "G11") (class "Default")
      (node (ref "GREEN") (pin "10") (pinfunction "OUT10_10") (pintype "bidirectional"))
      (node (ref "LED11") (pin "4") (pinfunction "G_4") (pintype "bidirectional"))
    )
    (net (code "45") (name "G12") (class "Default")
      (node (ref "GREEN") (pin "11") (pinfunction "OUT11_11") (pintype "bidirectional"))
      (node (ref "LED12") (pin "4") (pinfunction "G_4") (pintype "bidirectional"))
    )
    (net (code "46") (name "G13") (class "Default")
      (node (ref "GREEN") (pin "12") (pinfunction "OUT12_12") (pintype "bidirectional"))
      (node (ref "LED13") (pin "4") (pinfunction "G_4") (pintype "bidirectional"))
    )
    (net (code "47") (name "G14") (class "Default")
      (node (ref "GREEN") (pin "13") (pinfunction "OUT13_13") (pintype "bidirectional"))
      (node (ref "LED14") (pin "4") (pinfunction "G_4") (pintype "bidirectional"))
    )
    (net (code "48") (name "G15") (class "Default")
      (node (ref "GREEN") (pin "14") (pinfunction "OUT14_14") (pintype "bidirectional"))
      (node (ref "LED15") (pin "4") (pinfunction "G_4") (pintype "bidirectional"))
    )
    (net (code "49") (name "G16") (class "Default")
      (node (ref "GREEN") (pin "15") (pinfunction "OUT15_15") (pintype "bidirectional"))
      (node (ref "LED16") (pin "4") (pinfunction "G_4") (pintype "bidirectional"))
    )
    (net (code "50") (name "G17") (class "Default")
      (node (ref "GREEN2") (pin "28") (pinfunction "OUT0_28") (pintype "bidirectional"))
      (node (ref "LED17") (pin "4") (pinfunction "G_4") (pintype "bidirectional"))
    )
    (net (code "51") (name "G18") (class "Default")
      (node (ref "GREEN2") (pin "1") (pinfunction "OUT1_1") (pintype "bidirectional"))
      (node (ref "LED18") (pin "4") (pinfunction "G_4") (pintype "bidirectional"))
    )
    (net (code "52") (name "G19") (class "Default")
      (node (ref "GREEN2") (pin "2") (pinfunction "OUT2_2") (pintype "bidirectional"))
      (node (ref "LED19") (pin "4") (pinfunction "G_4") (pintype "bidirectional"))
    )
    (net (code "53") (name "G20") (class "Default")
      (node (ref "GREEN2") (pin "3") (pinfunction "OUT3_3") (pintype "bidirectional"))
      (node (ref "LED20") (pin "4") (pinfunction "G_4") (pintype "bidirectional"))
    )
    (net (code "54") (name "G21") (class "Default")
      (node (ref "GREEN2") (pin "4") (pinfunction "OUT4_4") (pintype "bidirectional"))
      (node (ref "LED21") (pin "4") (pinfunction "G_4") (pintype "bidirectional"))
    )
    (net (code "55") (name "G22") (class "Default")
      (node (ref "GREEN2") (pin "5") (pinfunction "OUT5_5") (pintype "bidirectional"))
      (node (ref "LED22") (pin "4") (pinfunction "G_4") (pintype "bidirectional"))
    )
    (net (code "56") (name "G23") (class "Default")
      (node (ref "GREEN2") (pin "6") (pinfunction "OUT6_6") (pintype "bidirectional"))
      (node (ref "LED23") (pin "4") (pinfunction "G_4") (pintype "bidirectional"))
    )
    (net (code "57") (name "G24") (class "Default")
      (node (ref "GREEN2") (pin "7") (pinfunction "OUT7_7") (pintype "bidirectional"))
      (node (ref "LED24") (pin "4") (pinfunction "G_4") (pintype "bidirectional"))
    )
    (net (code "58") (name "G25") (class "Default")
      (node (ref "GREEN2") (pin "8") (pinfunction "OUT8_8") (pintype "bidirectional"))
      (node (ref "LED25") (pin "4") (pinfunction "G_4") (pintype "bidirectional"))
    )
    (net (code "59") (name "G26") (class "Default")
      (node (ref "GREEN2") (pin "9") (pinfunction "OUT9_9") (pintype "bidirectional"))
      (node (ref "LED26") (pin "4") (pinfunction "G_4") (pintype "bidirectional"))
    )
    (net (code "60") (name "G27") (class "Default")
      (node (ref "GREEN2") (pin "10") (pinfunction "OUT10_10") (pintype "bidirectional"))
      (node (ref "LED27") (pin "4") (pinfunction "G_4") (pintype "bidirectional"))
    )
    (net (code "61") (name "G28") (class "Default")
      (node (ref "GREEN2") (pin "11") (pinfunction "OUT11_11") (pintype "bidirectional"))
      (node (ref "LED28") (pin "4") (pinfunction "G_4") (pintype "bidirectional"))
    )
    (net (code "62") (name "G29") (class "Default")
      (node (ref "GREEN2") (pin "12") (pinfunction "OUT12_12") (pintype "bidirectional"))
      (node (ref "LED29") (pin "4") (pinfunction "G_4") (pintype "bidirectional"))
    )
    (net (code "63") (name "G30") (class "Default")
      (node (ref "GREEN2") (pin "13") (pinfunction "OUT13_13") (pintype "bidirectional"))
      (node (ref "LED30") (pin "4") (pinfunction "G_4") (pintype "bidirectional"))
    )
    (net (code "64") (name "G31") (class "Default")
      (node (ref "GREEN2") (pin "14") (pinfunction "OUT14_14") (pintype "bidirectional"))
      (node (ref "LED31") (pin "4") (pinfunction "G_4") (pintype "bidirectional"))
    )
    (net (code "65") (name "G32") (class "Default")
      (node (ref "GREEN2") (pin "15") (pinfunction "OUT15_15") (pintype "bidirectional"))
      (node (ref "LED32") (pin "4") (pinfunction "G_4") (pintype "bidirectional"))
    )
    (net (code "66") (name "GND") (class "Default")
      (node (ref "BATT3") (pin "N1") (pinfunction "N1_N1") (pintype "bidirectional"))
      (node (ref "BATT3") (pin "N2") (pinfunction "N2_N2") (pintype "bidirectional"))
      (node (ref "BLUE") (pin "22") (pinfunction "GND_22") (pintype "bidirectional"))
      (node (ref "BLUE2") (pin "22") (pinfunction "GND_22") (pintype "bidirectional"))
      (node (ref "C1") (pin "1") (pinfunction "1_1") (pintype "passive"))
      (node (ref "C10") (pin "2") (pinfunction "2_2") (pintype "passive"))
      (node (ref "C2") (pin "1") (pinfunction "1_1") (pintype "passive"))
      (node (ref "C3") (pin "1") (pinfunction "1_1") (pintype "passive"))
      (node (ref "C5") (pin "1") (pinfunction "1_1") (pintype "passive"))
      (node (ref "C6") (pin "1") (pinfunction "1_1") (pintype "passive"))
      (node (ref "C7") (pin "1") (pinfunction "1_1") (pintype "passive"))
      (node (ref "C8") (pin "1") (pinfunction "1_1") (pintype "passive"))
      (node (ref "C9") (pin "2") (pinfunction "2_2") (pintype "passive"))
      (node (ref "GREEN") (pin "22") (pinfunction "GND_22") (pintype "bidirectional"))
      (node (ref "GREEN2") (pin "22") (pinfunction "GND_22") (pintype "bidirectional"))
      (node (ref "IC1") (pin "4") (pinfunction "GND_4") (pintype "power_in"))
      (node (ref "J2") (pin "20") (pinfunction "10_20") (pintype "passive"))
      (node (ref "R2") (pin "1") (pinfunction "1_1") (pintype "passive"))
      (node (ref "R4") (pin "1") (pinfunction "1_1") (pintype "passive"))
      (node (ref "R5") (pin "1") (pinfunction "1_1") (pintype "passive"))
      (node (ref "R6") (pin "1") (pinfunction "1_1") (pintype "passive"))
      (node (ref "R7") (pin "1") (pinfunction "1_1") (pintype "passive"))
      (node (ref "R8") (pin "1") (pinfunction "1_1") (pintype "passive"))
      (node (ref "RED") (pin "22") (pinfunction "GND_22") (pintype "bidirectional"))
      (node (ref "RED2") (pin "22") (pinfunction "GND_22") (pintype "bidirectional"))
      (node (ref "U$9") (pin "1") (pinfunction "GND_1") (pintype "bidirectional"))
      (node (ref "U$9") (pin "2") (pinfunction "EN_2") (pintype "bidirectional"))
      (node (ref "X2") (pin "2") (pinfunction "2_2") (pintype "bidirectional"))
    )
    (net (code "67") (name "Net-(BATT1-PadN1)") (class "Default")
      (node (ref "BATT1") (pin "N1") (pinfunction "N1_N1") (pintype "bidirectional"))
      (node (ref "BATT1") (pin "N2") (pinfunction "N2_N2") (pintype "bidirectional"))
      (node (ref "BATT2") (pin "P1") (pinfunction "P1_P1") (pintype "bidirectional"))
      (node (ref "BATT2") (pin "P2") (pinfunction "P2_P2") (pintype "bidirectional"))
    )
    (net (code "68") (name "Net-(BATT2-PadN1)") (class "Default")
      (node (ref "BATT2") (pin "N1") (pinfunction "N1_N1") (pintype "bidirectional"))
      (node (ref "BATT2") (pin "N2") (pinfunction "N2_N2") (pintype "bidirectional"))
      (node (ref "BATT3") (pin "P1") (pinfunction "P1_P1") (pintype "bidirectional"))
      (node (ref "BATT3") (pin "P2") (pinfunction "P2_P2") (pintype "bidirectional"))
    )
    (net (code "69") (name "Net-(BLUE-IREF)") (class "Default")
      (node (ref "BLUE") (pin "20") (pinfunction "IREF_20") (pintype "bidirectional"))
      (node (ref "R4") (pin "2") (pinfunction "2_2") (pintype "passive"))
    )
    (net (code "70") (name "Net-(BLUE2-IREF)") (class "Default")
      (node (ref "BLUE2") (pin "20") (pinfunction "IREF_20") (pintype "bidirectional"))
      (node (ref "R2") (pin "2") (pinfunction "2_2") (pintype "passive"))
    )
    (net (code "71") (name "Net-(GREEN-IREF)") (class "Default")
      (node (ref "GREEN") (pin "20") (pinfunction "IREF_20") (pintype "bidirectional"))
      (node (ref "R6") (pin "2") (pinfunction "2_2") (pintype "passive"))
    )
    (net (code "72") (name "Net-(GREEN2-IREF)") (class "Default")
      (node (ref "GREEN2") (pin "20") (pinfunction "IREF_20") (pintype "bidirectional"))
      (node (ref "R8") (pin "2") (pinfunction "2_2") (pintype "passive"))
    )
    (net (code "73") (name "Net-(RED-IREF)") (class "Default")
      (node (ref "R5") (pin "2") (pinfunction "2_2") (pintype "passive"))
      (node (ref "RED") (pin "20") (pinfunction "IREF_20") (pintype "bidirectional"))
    )
    (net (code "74") (name "Net-(RED2-IREF)") (class "Default")
      (node (ref "R7") (pin "2") (pinfunction "2_2") (pintype "passive"))
      (node (ref "RED2") (pin "20") (pinfunction "IREF_20") (pintype "bidirectional"))
    )
    (net (code "75") (name "P1.0{slash}CS") (class "Default")
      (node (ref "IC1") (pin "1") (pinfunction "~{CS}_1") (pintype "input"))
      (node (ref "J3") (pin "2") (pinfunction "2_2") (pintype "passive"))
    )
    (net (code "76") (name "P1.1{slash}SENSORDATA") (class "Default")
      (node (ref "J3") (pin "3") (pinfunction "3_3") (pintype "passive"))
      (node (ref "X2") (pin "3") (pinfunction "3_3") (pintype "bidirectional"))
    )
    (net (code "77") (name "P1.2{slash}BLANK") (class "Default")
      (node (ref "BLUE") (pin "23") (pinfunction "BLANK_23") (pintype "bidirectional"))
      (node (ref "BLUE2") (pin "23") (pinfunction "BLANK_23") (pintype "bidirectional"))
      (node (ref "GREEN") (pin "23") (pinfunction "BLANK_23") (pintype "bidirectional"))
      (node (ref "GREEN2") (pin "23") (pinfunction "BLANK_23") (pintype "bidirectional"))
      (node (ref "J3") (pin "4") (pinfunction "4_4") (pintype "passive"))
      (node (ref "RED") (pin "23") (pinfunction "BLANK_23") (pintype "bidirectional"))
      (node (ref "RED2") (pin "23") (pinfunction "BLANK_23") (pintype "bidirectional"))
    )
    (net (code "78") (name "P1.3{slash}VPRG") (class "Default")
      (node (ref "BLUE") (pin "27") (pinfunction "VPRG_27") (pintype "bidirectional"))
      (node (ref "BLUE2") (pin "27") (pinfunction "VPRG_27") (pintype "bidirectional"))
      (node (ref "GREEN") (pin "27") (pinfunction "VPRG_27") (pintype "bidirectional"))
      (node (ref "GREEN2") (pin "27") (pinfunction "VPRG_27") (pintype "bidirectional"))
      (node (ref "J3") (pin "5") (pinfunction "5_5") (pintype "passive"))
      (node (ref "RED") (pin "27") (pinfunction "VPRG_27") (pintype "bidirectional"))
      (node (ref "RED2") (pin "27") (pinfunction "VPRG_27") (pintype "bidirectional"))
    )
    (net (code "79") (name "P1.4{slash}GSCLK") (class "Default")
      (node (ref "BLUE") (pin "18") (pinfunction "GSCLK_18") (pintype "bidirectional"))
      (node (ref "BLUE2") (pin "18") (pinfunction "GSCLK_18") (pintype "bidirectional"))
      (node (ref "GREEN") (pin "18") (pinfunction "GSCLK_18") (pintype "bidirectional"))
      (node (ref "GREEN2") (pin "18") (pinfunction "GSCLK_18") (pintype "bidirectional"))
      (node (ref "J3") (pin "6") (pinfunction "6_6") (pintype "passive"))
      (node (ref "RED") (pin "18") (pinfunction "GSCLK_18") (pintype "bidirectional"))
      (node (ref "RED2") (pin "18") (pinfunction "GSCLK_18") (pintype "bidirectional"))
    )
    (net (code "80") (name "P1.5{slash}UCB0CLK") (class "Default")
      (node (ref "IC1") (pin "6") (pinfunction "SCK_6") (pintype "input"))
      (node (ref "J3") (pin "7") (pinfunction "7_7") (pintype "passive"))
    )
    (net (code "81") (name "P1.6{slash}UCB0SOMI") (class "Default")
      (node (ref "IC1") (pin "2") (pinfunction "SO_2") (pintype "bidirectional"))
      (node (ref "J2") (pin "14") (pinfunction "4_14") (pintype "passive"))
    )
    (net (code "82") (name "P1.7{slash}UCB0SIMO") (class "Default")
      (node (ref "IC1") (pin "5") (pinfunction "SI_5") (pintype "input"))
      (node (ref "J2") (pin "15") (pinfunction "5_15") (pintype "passive"))
    )
    (net (code "83") (name "P2.0{slash}SCLK") (class "Default")
      (node (ref "BLUE") (pin "25") (pinfunction "SCLK_25") (pintype "bidirectional"))
      (node (ref "BLUE2") (pin "25") (pinfunction "SCLK_25") (pintype "bidirectional"))
      (node (ref "GREEN") (pin "25") (pinfunction "SCLK_25") (pintype "bidirectional"))
      (node (ref "GREEN2") (pin "25") (pinfunction "SCLK_25") (pintype "bidirectional"))
      (node (ref "J3") (pin "8") (pinfunction "8_8") (pintype "passive"))
      (node (ref "RED") (pin "25") (pinfunction "SCLK_25") (pintype "bidirectional"))
      (node (ref "RED2") (pin "25") (pinfunction "SCLK_25") (pintype "bidirectional"))
    )
    (net (code "84") (name "P2.1{slash}XLAT") (class "Default")
      (node (ref "BLUE") (pin "24") (pinfunction "XLAT_24") (pintype "bidirectional"))
      (node (ref "BLUE2") (pin "24") (pinfunction "XLAT_24") (pintype "bidirectional"))
      (node (ref "GREEN") (pin "24") (pinfunction "XLAT_24") (pintype "bidirectional"))
      (node (ref "GREEN2") (pin "24") (pinfunction "XLAT_24") (pintype "bidirectional"))
      (node (ref "J3") (pin "9") (pinfunction "9_9") (pintype "passive"))
      (node (ref "RED") (pin "24") (pinfunction "XLAT_24") (pintype "bidirectional"))
      (node (ref "RED2") (pin "24") (pinfunction "XLAT_24") (pintype "bidirectional"))
    )
    (net (code "85") (name "P2.2{slash}SIN1") (class "Default")
      (node (ref "GREEN") (pin "26") (pinfunction "SIN_26") (pintype "bidirectional"))
      (node (ref "J3") (pin "10") (pinfunction "10_10") (pintype "passive"))
    )
    (net (code "86") (name "P2.3{slash}SIN2") (class "Default")
      (node (ref "GREEN2") (pin "26") (pinfunction "SIN_26") (pintype "bidirectional"))
      (node (ref "J2") (pin "11") (pinfunction "1_11") (pintype "passive"))
    )
    (net (code "87") (name "P2.4{slash}SIN3") (class "Default")
      (node (ref "J2") (pin "12") (pinfunction "2_12") (pintype "passive"))
      (node (ref "RED") (pin "26") (pinfunction "SIN_26") (pintype "bidirectional"))
    )
    (net (code "88") (name "P2.5{slash}SIN4") (class "Default")
      (node (ref "J2") (pin "13") (pinfunction "3_13") (pintype "passive"))
      (node (ref "RED2") (pin "26") (pinfunction "SIN_26") (pintype "bidirectional"))
    )
    (net (code "89") (name "R1") (class "Default")
      (node (ref "LED1") (pin "3") (pinfunction "R_3") (pintype "passive"))
      (node (ref "RED") (pin "28") (pinfunction "OUT0_28") (pintype "bidirectional"))
    )
    (net (code "90") (name "R2") (class "Default")
      (node (ref "LED2") (pin "3") (pinfunction "R_3") (pintype "passive"))
      (node (ref "RED") (pin "1") (pinfunction "OUT1_1") (pintype "bidirectional"))
    )
    (net (code "91") (name "R3") (class "Default")
      (node (ref "LED3") (pin "3") (pinfunction "R_3") (pintype "passive"))
      (node (ref "RED") (pin "2") (pinfunction "OUT2_2") (pintype "bidirectional"))
    )
    (net (code "92") (name "R4") (class "Default")
      (node (ref "LED4") (pin "3") (pinfunction "R_3") (pintype "passive"))
      (node (ref "RED") (pin "3") (pinfunction "OUT3_3") (pintype "bidirectional"))
    )
    (net (code "93") (name "R5") (class "Default")
      (node (ref "LED5") (pin "3") (pinfunction "R_3") (pintype "passive"))
      (node (ref "RED") (pin "4") (pinfunction "OUT4_4") (pintype "bidirectional"))
    )
    (net (code "94") (name "R6") (class "Default")
      (node (ref "LED6") (pin "3") (pinfunction "R_3") (pintype "passive"))
      (node (ref "RED") (pin "5") (pinfunction "OUT5_5") (pintype "bidirectional"))
    )
    (net (code "95") (name "R7") (class "Default")
      (node (ref "LED7") (pin "3") (pinfunction "R_3") (pintype "passive"))
      (node (ref "RED") (pin "6") (pinfunction "OUT6_6") (pintype "bidirectional"))
    )
    (net (code "96") (name "R8") (class "Default")
      (node (ref "LED8") (pin "3") (pinfunction "R_3") (pintype "passive"))
      (node (ref "RED") (pin "7") (pinfunction "OUT7_7") (pintype "bidirectional"))
    )
    (net (code "97") (name "R9") (class "Default")
      (node (ref "LED9") (pin "3") (pinfunction "R_3") (pintype "passive"))
      (node (ref "RED") (pin "8") (pinfunction "OUT8_8") (pintype "bidirectional"))
    )
    (net (code "98") (name "R10") (class "Default")
      (node (ref "LED10") (pin "3") (pinfunction "R_3") (pintype "passive"))
      (node (ref "RED") (pin "9") (pinfunction "OUT9_9") (pintype "bidirectional"))
    )
    (net (code "99") (name "R11") (class "Default")
      (node (ref "LED11") (pin "3") (pinfunction "R_3") (pintype "passive"))
      (node (ref "RED") (pin "10") (pinfunction "OUT10_10") (pintype "bidirectional"))
    )
    (net (code "100") (name "R12") (class "Default")
      (node (ref "LED12") (pin "3") (pinfunction "R_3") (pintype "passive"))
      (node (ref "RED") (pin "11") (pinfunction "OUT11_11") (pintype "bidirectional"))
    )
    (net (code "101") (name "R13") (class "Default")
      (node (ref "LED13") (pin "3") (pinfunction "R_3") (pintype "passive"))
      (node (ref "RED") (pin "12") (pinfunction "OUT12_12") (pintype "bidirectional"))
    )
    (net (code "102") (name "R14") (class "Default")
      (node (ref "LED14") (pin "3") (pinfunction "R_3") (pintype "passive"))
      (node (ref "RED") (pin "13") (pinfunction "OUT13_13") (pintype "bidirectional"))
    )
    (net (code "103") (name "R15") (class "Default")
      (node (ref "LED15") (pin "3") (pinfunction "R_3") (pintype "passive"))
      (node (ref "RED") (pin "14") (pinfunction "OUT14_14") (pintype "bidirectional"))
    )
    (net (code "104") (name "R16") (class "Default")
      (node (ref "LED16") (pin "3") (pinfunction "R_3") (pintype "passive"))
      (node (ref "RED") (pin "15") (pinfunction "OUT15_15") (pintype "bidirectional"))
    )
    (net (code "105") (name "R17") (class "Default")
      (node (ref "LED17") (pin "3") (pinfunction "R_3") (pintype "passive"))
      (node (ref "RED2") (pin "28") (pinfunction "OUT0_28") (pintype "bidirectional"))
    )
    (net (code "106") (name "R18") (class "Default")
      (node (ref "LED18") (pin "3") (pinfunction "R_3") (pintype "passive"))
      (node (ref "RED2") (pin "1") (pinfunction "OUT1_1") (pintype "bidirectional"))
    )
    (net (code "107") (name "R19") (class "Default")
      (node (ref "LED19") (pin "3") (pinfunction "R_3") (pintype "passive"))
      (node (ref "RED2") (pin "2") (pinfunction "OUT2_2") (pintype "bidirectional"))
    )
    (net (code "108") (name "R20") (class "Default")
      (node (ref "LED20") (pin "3") (pinfunction "R_3") (pintype "passive"))
      (node (ref "RED2") (pin "3") (pinfunction "OUT3_3") (pintype "bidirectional"))
    )
    (net (code "109") (name "R21") (class "Default")
      (node (ref "LED21") (pin "3") (pinfunction "R_3") (pintype "passive"))
      (node (ref "RED2") (pin "4") (pinfunction "OUT4_4") (pintype "bidirectional"))
    )
    (net (code "110") (name "R22") (class "Default")
      (node (ref "LED22") (pin "3") (pinfunction "R_3") (pintype "passive"))
      (node (ref "RED2") (pin "5") (pinfunction "OUT5_5") (pintype "bidirectional"))
    )
    (net (code "111") (name "R23") (class "Default")
      (node (ref "LED23") (pin "3") (pinfunction "R_3") (pintype "passive"))
      (node (ref "RED2") (pin "6") (pinfunction "OUT6_6") (pintype "bidirectional"))
    )
    (net (code "112") (name "R24") (class "Default")
      (node (ref "LED24") (pin "3") (pinfunction "R_3") (pintype "passive"))
      (node (ref "RED2") (pin "7") (pinfunction "OUT7_7") (pintype "bidirectional"))
    )
    (net (code "113") (name "R25") (class "Default")
      (node (ref "LED25") (pin "3") (pinfunction "R_3") (pintype "passive"))
      (node (ref "RED2") (pin "8") (pinfunction "OUT8_8") (pintype "bidirectional"))
    )
    (net (code "114") (name "R26") (class "Default")
      (node (ref "LED26") (pin "3") (pinfunction "R_3") (pintype "passive"))
      (node (ref "RED2") (pin "9") (pinfunction "OUT9_9") (pintype "bidirectional"))
    )
    (net (code "115") (name "R27") (class "Default")
      (node (ref "LED27") (pin "3") (pinfunction "R_3") (pintype "passive"))
      (node (ref "RED2") (pin "10") (pinfunction "OUT10_10") (pintype "bidirectional"))
    )
    (net (code "116") (name "R28") (class "Default")
      (node (ref "LED28") (pin "3") (pinfunction "R_3") (pintype "passive"))
      (node (ref "RED2") (pin "11") (pinfunction "OUT11_11") (pintype "bidirectional"))
    )
    (net (code "117") (name "R29") (class "Default")
      (node (ref "LED29") (pin "3") (pinfunction "R_3") (pintype "passive"))
      (node (ref "RED2") (pin "12") (pinfunction "OUT12_12") (pintype "bidirectional"))
    )
    (net (code "118") (name "R30") (class "Default")
      (node (ref "LED30") (pin "3") (pinfunction "R_3") (pintype "passive"))
      (node (ref "RED2") (pin "13") (pinfunction "OUT13_13") (pintype "bidirectional"))
    )
    (net (code "119") (name "R31") (class "Default")
      (node (ref "LED31") (pin "3") (pinfunction "R_3") (pintype "passive"))
      (node (ref "RED2") (pin "14") (pinfunction "OUT14_14") (pintype "bidirectional"))
    )
    (net (code "120") (name "R32") (class "Default")
      (node (ref "LED32") (pin "3") (pinfunction "R_3") (pintype "passive"))
      (node (ref "RED2") (pin "15") (pinfunction "OUT15_15") (pintype "bidirectional"))
    )
    (net (code "121") (name "RST{slash}SBWTDIO") (class "Default")
      (node (ref "J2") (pin "16") (pinfunction "6_16") (pintype "passive"))
    )
    (net (code "122") (name "TEST{slash}SBWTCK") (class "Default")
      (node (ref "J2") (pin "17") (pinfunction "7_17") (pintype "passive"))
    )
    (net (code "123") (name "VCC") (class "Default")
      (node (ref "BATT1") (pin "P1") (pinfunction "P1_P1") (pintype "bidirectional"))
      (node (ref "BATT1") (pin "P2") (pinfunction "P2_P2") (pintype "bidirectional"))
      (node (ref "C3") (pin "2") (pinfunction "2_2") (pintype "passive"))
      (node (ref "C9") (pin "1") (pinfunction "1_1") (pintype "passive"))
      (node (ref "U$9") (pin "3") (pinfunction "IN1_3") (pintype "bidirectional"))
      (node (ref "U$9") (pin "4") (pinfunction "IN2_4") (pintype "bidirectional"))
      (node (ref "X2") (pin "1") (pinfunction "1_1") (pintype "bidirectional"))
    )
    (net (code "124") (name "XIN{slash}P2.6{slash}SIN5") (class "Default")
      (node (ref "BLUE") (pin "26") (pinfunction "SIN_26") (pintype "bidirectional"))
      (node (ref "J2") (pin "19") (pinfunction "9_19") (pintype "passive"))
    )
    (net (code "125") (name "XOUT{slash}P2.7{slash}SIN6") (class "Default")
      (node (ref "BLUE2") (pin "26") (pinfunction "SIN_26") (pintype "bidirectional"))
      (node (ref "J2") (pin "18") (pinfunction "8_18") (pintype "passive"))
    )
    (net (code "126") (name "unconnected-(BLUE-SOUT-Pad17)") (class "Default")
      (node (ref "BLUE") (pin "17") (pinfunction "SOUT_17") (pintype "bidirectional"))
    )
    (net (code "127") (name "unconnected-(BLUE-XERR-Pad16)") (class "Default")
      (node (ref "BLUE") (pin "16") (pinfunction "XERR_16") (pintype "bidirectional"))
    )
    (net (code "128") (name "unconnected-(BLUE2-SOUT-Pad17)") (class "Default")
      (node (ref "BLUE2") (pin "17") (pinfunction "SOUT_17") (pintype "bidirectional"))
    )
    (net (code "129") (name "unconnected-(BLUE2-XERR-Pad16)") (class "Default")
      (node (ref "BLUE2") (pin "16") (pinfunction "XERR_16") (pintype "bidirectional"))
    )
    (net (code "130") (name "unconnected-(GREEN-SOUT-Pad17)") (class "Default")
      (node (ref "GREEN") (pin "17") (pinfunction "SOUT_17") (pintype "bidirectional"))
    )
    (net (code "131") (name "unconnected-(GREEN-XERR-Pad16)") (class "Default")
      (node (ref "GREEN") (pin "16") (pinfunction "XERR_16") (pintype "bidirectional"))
    )
    (net (code "132") (name "unconnected-(GREEN2-SOUT-Pad17)") (class "Default")
      (node (ref "GREEN2") (pin "17") (pinfunction "SOUT_17") (pintype "bidirectional"))
    )
    (net (code "133") (name "unconnected-(GREEN2-XERR-Pad16)") (class "Default")
      (node (ref "GREEN2") (pin "16") (pinfunction "XERR_16") (pintype "bidirectional"))
    )
    (net (code "134") (name "unconnected-(RED-SOUT-Pad17)") (class "Default")
      (node (ref "RED") (pin "17") (pinfunction "SOUT_17") (pintype "bidirectional"))
    )
    (net (code "135") (name "unconnected-(RED-XERR-Pad16)") (class "Default")
      (node (ref "RED") (pin "16") (pinfunction "XERR_16") (pintype "bidirectional"))
    )
    (net (code "136") (name "unconnected-(RED2-SOUT-Pad17)") (class "Default")
      (node (ref "RED2") (pin "17") (pinfunction "SOUT_17") (pintype "bidirectional"))
    )
    (net (code "137") (name "unconnected-(RED2-XERR-Pad16)") (class "Default")
      (node (ref "RED2") (pin "16") (pinfunction "XERR_16") (pintype "bidirectional"))
    )
    (net (code "138") (name "unconnected-(U$9-RESET-Pad8)") (class "Default")
      (node (ref "U$9") (pin "8") (pinfunction "RESET_8") (pintype "bidirectional"))
    )
  )
)
